# sensebox.net
KiCad netlist of a schematic drawn in EAGLE
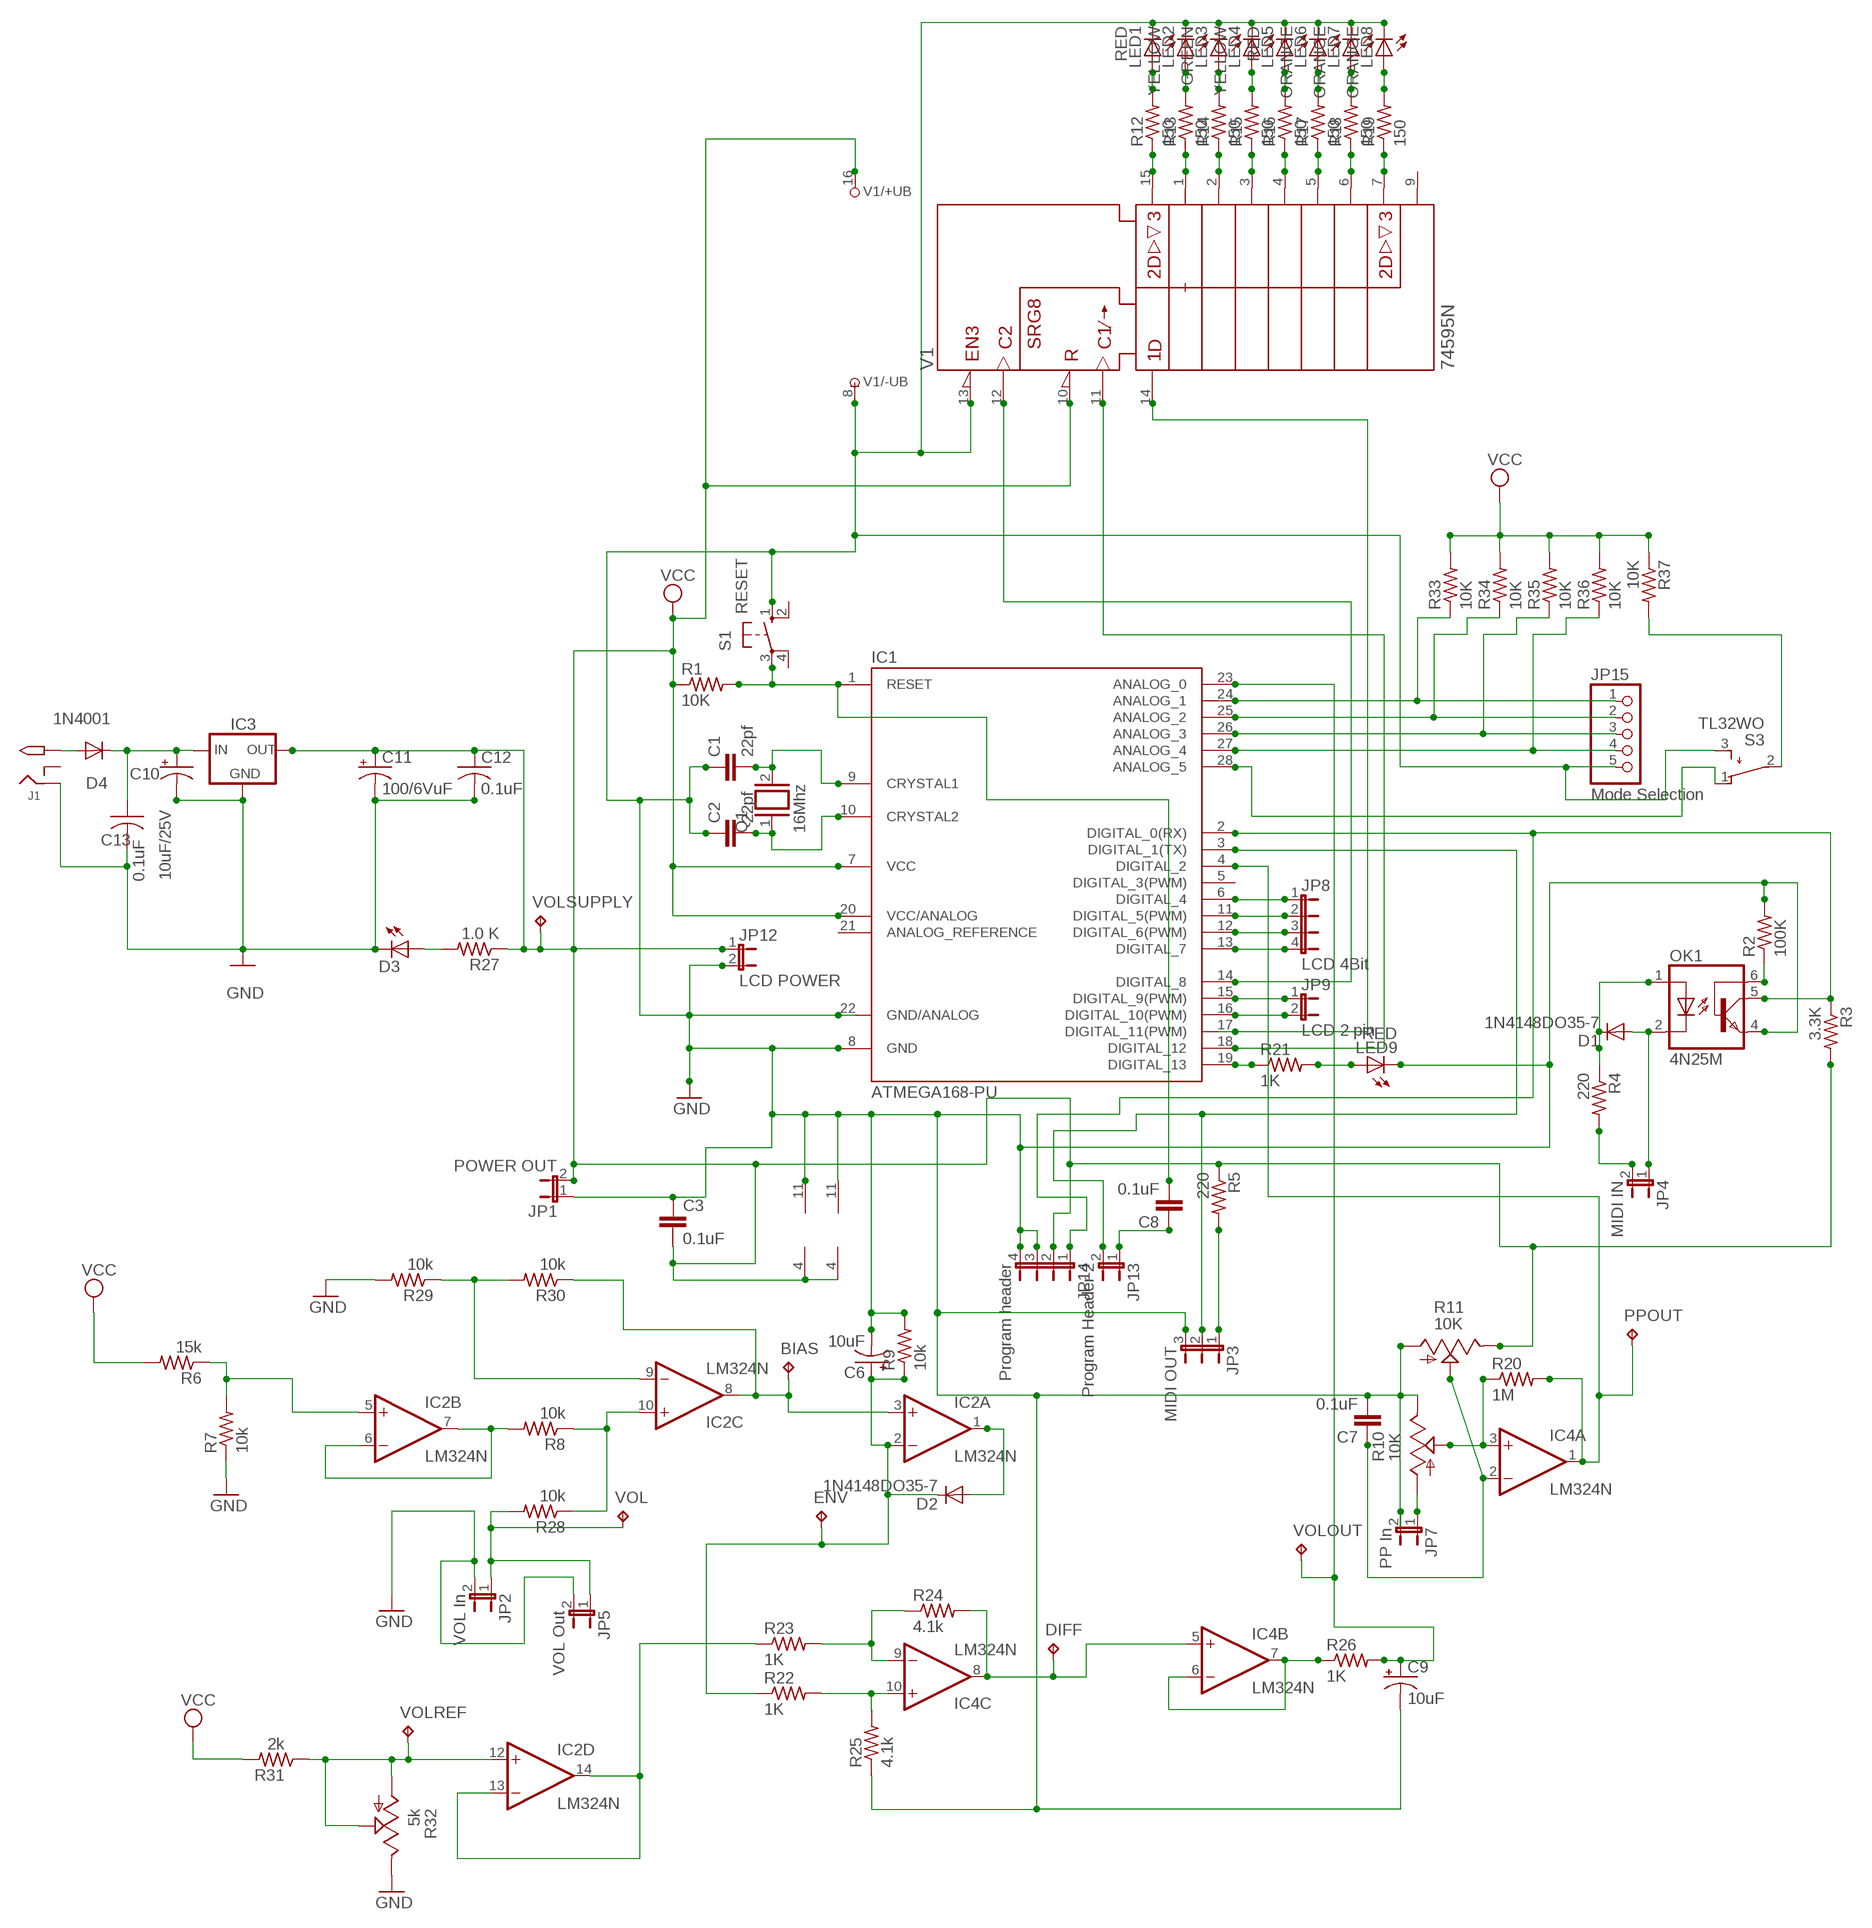
[diagram p0: schematic, sheet 1]

(export (version "E")
  (design (tool "Eeschema 10.0.6"))
  (components
    (comp (ref "BIAS")
      (value "TP1X1")
      (footprint "eagle-import:TP1X1")
      (libsource (lib "eagle-import") (part "TP1X1"))
    )
    (comp (ref "C1")
      (value "22pf")
      (footprint "eagle-import:C2.5-2")
      (libsource (lib "eagle-import") (part "C2.5/2"))
    )
    (comp (ref "C2")
      (value "22pf")
      (footprint "eagle-import:C2.5-2")
      (libsource (lib "eagle-import") (part "C2.5/2"))
    )
    (comp (ref "C3")
      (value "0.1uF")
      (footprint "eagle-import:C5B2.5")
      (libsource (lib "eagle-import") (part "C5/2.5"))
    )
    (comp (ref "C6")
      (value "10uF")
      (footprint "eagle-import:E5-8,5")
      (libsource (lib "eagle-import") (part "rcl_CPOL-USE5-8.5"))
    )
    (comp (ref "C7")
      (value "0.1uF")
      (footprint "eagle-import:C5B2.5")
      (libsource (lib "eagle-import") (part "C5/2.5"))
    )
    (comp (ref "C8")
      (value "0.1uF")
      (footprint "eagle-import:C2.5-2")
      (libsource (lib "eagle-import") (part "C2.5/2"))
    )
    (comp (ref "C9")
      (value "10uF")
      (footprint "eagle-import:E5-8,5")
      (libsource (lib "eagle-import") (part "rcl_CPOL-USE5-8.5"))
    )
    (comp (ref "C10")
      (value "10uF/25V")
      (footprint "eagle-import:E2,5-6")
      (libsource (lib "eagle-import") (part "CPOL-USE2.5-6"))
    )
    (comp (ref "C11")
      (value "100/6VuF")
      (footprint "eagle-import:E2,5-6")
      (libsource (lib "eagle-import") (part "CPOL-USE2.5-6"))
    )
    (comp (ref "C12")
      (value "0.1uF")
      (footprint "eagle-import:C025-025X050")
      (libsource (lib "eagle-import") (part "C-US025-025X050"))
    )
    (comp (ref "C13")
      (value "0.1uF")
      (footprint "eagle-import:C025-025X050")
      (libsource (lib "eagle-import") (part "C-US025-025X050"))
    )
    (comp (ref "D1")
      (value "1N4148DO35-7")
      (footprint "eagle-import:DO35-7")
      (libsource (lib "eagle-import") (part "1N4148DO35-7"))
    )
    (comp (ref "D2")
      (value "1N4148DO35-7")
      (footprint "eagle-import:DO35-7")
      (libsource (lib "eagle-import") (part "1N4148DO35-7"))
    )
    (comp (ref "D3")
      (value "GREEN")
      (footprint "eagle-import:LED3MM")
      (libsource (lib "eagle-import") (part "minimidi_LED3MM"))
    )
    (comp (ref "D4")
      (value "1N4001")
      (footprint "eagle-import:DO41-10")
      (libsource (lib "eagle-import") (part "1N4004"))
    )
    (comp (ref "DIFF")
      (value "TP1X1")
      (footprint "eagle-import:TP1X1")
      (libsource (lib "eagle-import") (part "TP1X1"))
    )
    (comp (ref "ENV")
      (value "TP1X1")
      (footprint "eagle-import:TP1X1")
      (libsource (lib "eagle-import") (part "TP1X1"))
    )
    (comp (ref "IC1")
      (value "ATMEGA168-PU")
      (footprint "eagle-import:DIL28-3")
      (libsource (lib "eagle-import") (part "ATMEGA168-PU"))
    )
    (comp (ref "IC2")
      (value "LM324N")
      (footprint "eagle-import:DIL14")
      (libsource (lib "eagle-import") (part "LM324N"))
    )
    (comp (ref "IC3")
      (value "+5v 7805")
      (footprint "eagle-import:78XXS")
      (libsource (lib "eagle-import") (part "78XXS"))
    )
    (comp (ref "IC4")
      (value "LM324N")
      (footprint "eagle-import:DIL14")
      (libsource (lib "eagle-import") (part "LM324N"))
    )
    (comp (ref "J1")
      (value "2.1MMJACK")
      (footprint "eagle-import:PJ-102A")
      (libsource (lib "eagle-import") (part "2.1MMJACK"))
    )
    (comp (ref "JP1")
      (value "POWER OUT")
      (footprint "eagle-import:JP1")
      (libsource (lib "eagle-import") (part "JP1E"))
    )
    (comp (ref "JP2")
      (value "VOL In")
      (footprint "eagle-import:JP1")
      (libsource (lib "eagle-import") (part "JP1E"))
    )
    (comp (ref "JP3")
      (value "MIDI OUT")
      (footprint "eagle-import:JP2")
      (libsource (lib "eagle-import") (part "JP2E"))
    )
    (comp (ref "JP4")
      (value "MIDI IN")
      (footprint "eagle-import:JP1")
      (libsource (lib "eagle-import") (part "JP1E"))
    )
    (comp (ref "JP5")
      (value "VOL Out")
      (footprint "eagle-import:JP1")
      (libsource (lib "eagle-import") (part "JP1E"))
    )
    (comp (ref "JP7")
      (value "PP In")
      (footprint "eagle-import:JP1")
      (libsource (lib "eagle-import") (part "JP1E"))
    )
    (comp (ref "JP8")
      (value "LCD 4Bit")
      (footprint "eagle-import:JP4")
      (libsource (lib "eagle-import") (part "JP4E"))
    )
    (comp (ref "JP9")
      (value "LCD 2 pin")
      (footprint "eagle-import:JP1")
      (libsource (lib "eagle-import") (part "JP1E"))
    )
    (comp (ref "JP12")
      (value "LCD POWER")
      (footprint "eagle-import:JP1")
      (libsource (lib "eagle-import") (part "JP1E"))
    )
    (comp (ref "JP13")
      (value "Program Header 2")
      (footprint "eagle-import:JP1")
      (libsource (lib "eagle-import") (part "JP1E"))
    )
    (comp (ref "JP14")
      (value "Program header")
      (footprint "eagle-import:JP4")
      (libsource (lib "eagle-import") (part "JP4E"))
    )
    (comp (ref "JP15")
      (value "Mode Selection")
      (footprint "eagle-import:1X05")
      (libsource (lib "eagle-import") (part "PINHD-1X5"))
    )
    (comp (ref "LED1")
      (value "RED")
      (footprint "eagle-import:LED5MM")
      (libsource (lib "eagle-import") (part "LED5MM"))
    )
    (comp (ref "LED2")
      (value "YELLOW")
      (footprint "eagle-import:LED5MM")
      (libsource (lib "eagle-import") (part "LED5MM"))
    )
    (comp (ref "LED3")
      (value "GREEN")
      (footprint "eagle-import:LED5MM")
      (libsource (lib "eagle-import") (part "LED5MM"))
    )
    (comp (ref "LED4")
      (value "YELLOW")
      (footprint "eagle-import:LED5MM")
      (libsource (lib "eagle-import") (part "LED5MM"))
    )
    (comp (ref "LED5")
      (value "RED")
      (footprint "eagle-import:LED5MM")
      (libsource (lib "eagle-import") (part "LED5MM"))
    )
    (comp (ref "LED6")
      (value "ORANGE")
      (footprint "eagle-import:LED5MM")
      (libsource (lib "eagle-import") (part "LED5MM"))
    )
    (comp (ref "LED7")
      (value "ORANGE")
      (footprint "eagle-import:LED5MM")
      (libsource (lib "eagle-import") (part "LED5MM"))
    )
    (comp (ref "LED8")
      (value "ORANGE")
      (footprint "eagle-import:LED5MM")
      (libsource (lib "eagle-import") (part "LED5MM"))
    )
    (comp (ref "LED9")
      (value "RED")
      (footprint "eagle-import:LED5MM")
      (libsource (lib "eagle-import") (part "LED5MM"))
    )
    (comp (ref "OK1")
      (value "4N25M")
      (footprint "eagle-import:DIL06")
      (libsource (lib "eagle-import") (part "4N?M25"))
    )
    (comp (ref "PPOUT")
      (value "TP1X1")
      (footprint "eagle-import:TP1X1")
      (libsource (lib "eagle-import") (part "TP1X1"))
    )
    (comp (ref "Q1")
      (value "16Mhz")
      (footprint "eagle-import:Q")
      (libsource (lib "eagle-import") (part "XTAL"))
    )
    (comp (ref "R1")
      (value "10K")
      (footprint "eagle-import:0207_7")
      (libsource (lib "eagle-import") (part "resistor_R-US_0207/7"))
    )
    (comp (ref "R2")
      (value "100K")
      (footprint "eagle-import:0207_7")
      (libsource (lib "eagle-import") (part "resistor_R-US_0207/7"))
    )
    (comp (ref "R3")
      (value "3.3K")
      (footprint "eagle-import:0207_7")
      (libsource (lib "eagle-import") (part "resistor_R-US_0207/7"))
    )
    (comp (ref "R4")
      (value "220")
      (footprint "eagle-import:0207_7")
      (libsource (lib "eagle-import") (part "resistor_R-US_0207/7"))
    )
    (comp (ref "R5")
      (value "220")
      (footprint "eagle-import:0207_7")
      (libsource (lib "eagle-import") (part "resistor_R-US_0207/7"))
    )
    (comp (ref "R6")
      (value "15k")
      (footprint "eagle-import:0207_10")
      (libsource (lib "eagle-import") (part "rcl_R-US_0207/10"))
    )
    (comp (ref "R7")
      (value "10k")
      (footprint "eagle-import:0207_10")
      (libsource (lib "eagle-import") (part "rcl_R-US_0207/10"))
    )
    (comp (ref "R8")
      (value "10k")
      (footprint "eagle-import:0207_10")
      (libsource (lib "eagle-import") (part "rcl_R-US_0207/10"))
    )
    (comp (ref "R9")
      (value "10k")
      (footprint "eagle-import:0207_7")
      (libsource (lib "eagle-import") (part "resistor_R-US_0207/7"))
    )
    (comp (ref "R10")
      (value "10K")
      (footprint "eagle-import:B64Y")
      (libsource (lib "eagle-import") (part "TRIM_US-B64Y"))
    )
    (comp (ref "R11")
      (value "10K")
      (footprint "eagle-import:B64Y")
      (libsource (lib "eagle-import") (part "TRIM_US-B64Y"))
    )
    (comp (ref "R12")
      (value "150")
      (footprint "eagle-import:0207_7")
      (libsource (lib "eagle-import") (part "resistor_R-US_0207/7"))
    )
    (comp (ref "R13")
      (value "150")
      (footprint "eagle-import:0207_7")
      (libsource (lib "eagle-import") (part "resistor_R-US_0207/7"))
    )
    (comp (ref "R14")
      (value "150")
      (footprint "eagle-import:0207_7")
      (libsource (lib "eagle-import") (part "resistor_R-US_0207/7"))
    )
    (comp (ref "R15")
      (value "150")
      (footprint "eagle-import:0207_7")
      (libsource (lib "eagle-import") (part "resistor_R-US_0207/7"))
    )
    (comp (ref "R16")
      (value "150")
      (footprint "eagle-import:0207_7")
      (libsource (lib "eagle-import") (part "resistor_R-US_0207/7"))
    )
    (comp (ref "R17")
      (value "150")
      (footprint "eagle-import:0207_7")
      (libsource (lib "eagle-import") (part "resistor_R-US_0207/7"))
    )
    (comp (ref "R18")
      (value "150")
      (footprint "eagle-import:0207_7")
      (libsource (lib "eagle-import") (part "resistor_R-US_0207/7"))
    )
    (comp (ref "R19")
      (value "150")
      (footprint "eagle-import:0207_7")
      (libsource (lib "eagle-import") (part "resistor_R-US_0207/7"))
    )
    (comp (ref "R20")
      (value "1M")
      (footprint "eagle-import:0207_7")
      (libsource (lib "eagle-import") (part "resistor_R-US_0207/7"))
    )
    (comp (ref "R21")
      (value "1K")
      (footprint "eagle-import:0207_7")
      (libsource (lib "eagle-import") (part "resistor_R-US_0207/7"))
    )
    (comp (ref "R22")
      (value "1K")
      (footprint "eagle-import:0207_7")
      (libsource (lib "eagle-import") (part "resistor_R-US_0207/7"))
    )
    (comp (ref "R23")
      (value "1K")
      (footprint "eagle-import:0207_7")
      (libsource (lib "eagle-import") (part "resistor_R-US_0207/7"))
    )
    (comp (ref "R24")
      (value "4.1k")
      (footprint "eagle-import:0207_7")
      (libsource (lib "eagle-import") (part "resistor_R-US_0207/7"))
    )
    (comp (ref "R25")
      (value "4.1k")
      (footprint "eagle-import:0207_7")
      (libsource (lib "eagle-import") (part "resistor_R-US_0207/7"))
    )
    (comp (ref "R26")
      (value "1K")
      (footprint "eagle-import:0207_7")
      (libsource (lib "eagle-import") (part "resistor_R-US_0207/7"))
    )
    (comp (ref "R27")
      (value "1.0 K")
      (footprint "eagle-import:0207_5V")
      (libsource (lib "eagle-import") (part "R-US_0207/5V"))
    )
    (comp (ref "R28")
      (value "10k")
      (footprint "eagle-import:0207_10")
      (libsource (lib "eagle-import") (part "resistor_R-US_0207/10"))
    )
    (comp (ref "R29")
      (value "10k")
      (footprint "eagle-import:0207_10")
      (libsource (lib "eagle-import") (part "rcl_R-US_0207/10"))
    )
    (comp (ref "R30")
      (value "10k")
      (footprint "eagle-import:0207_10")
      (libsource (lib "eagle-import") (part "resistor_R-US_0207/10"))
    )
    (comp (ref "R31")
      (value "2k")
      (footprint "eagle-import:0207_10")
      (libsource (lib "eagle-import") (part "rcl_R-US_0207/10"))
    )
    (comp (ref "R32")
      (value "5k")
      (footprint "eagle-import:B64Y")
      (libsource (lib "eagle-import") (part "TRIM_US-B64Y"))
    )
    (comp (ref "R33")
      (value "10K")
      (footprint "eagle-import:0207_7")
      (libsource (lib "eagle-import") (part "resistor_R-US_0207/7"))
    )
    (comp (ref "R34")
      (value "10K")
      (footprint "eagle-import:0207_7")
      (libsource (lib "eagle-import") (part "resistor_R-US_0207/7"))
    )
    (comp (ref "R35")
      (value "10K")
      (footprint "eagle-import:0207_7")
      (libsource (lib "eagle-import") (part "resistor_R-US_0207/7"))
    )
    (comp (ref "R36")
      (value "10K")
      (footprint "eagle-import:0207_7")
      (libsource (lib "eagle-import") (part "resistor_R-US_0207/7"))
    )
    (comp (ref "R37")
      (value "10K")
      (footprint "eagle-import:0207_7")
      (libsource (lib "eagle-import") (part "resistor_R-US_0207/7"))
    )
    (comp (ref "S1")
      (value "RESET")
      (footprint "eagle-import:B3F-10XX")
      (libsource (lib "eagle-import") (part "10-XX"))
    )
    (comp (ref "S3")
      (value "TL32WO")
      (footprint "eagle-import:TL3XWO")
      (libsource (lib "eagle-import") (part "TL32WO"))
    )
    (comp (ref "V1")
      (value "74595N")
      (footprint "eagle-import:DIL16")
      (libsource (lib "eagle-import") (part "74595N"))
    )
    (comp (ref "VOL")
      (value "TP1X1")
      (footprint "eagle-import:TP1X1")
      (libsource (lib "eagle-import") (part "TP1X1"))
    )
    (comp (ref "VOLOUT")
      (value "TP1X1")
      (footprint "eagle-import:TP1X1")
      (libsource (lib "eagle-import") (part "TP1X1"))
    )
    (comp (ref "VOLREF")
      (value "TP1X1")
      (footprint "eagle-import:TP1X1")
      (libsource (lib "eagle-import") (part "TP1X1"))
    )
    (comp (ref "VOLSUPPLY")
      (value "TP1X1")
      (footprint "eagle-import:TP1X1")
      (libsource (lib "eagle-import") (part "TP1X1"))
    )
  )
  (nets
    (net (code "1") (name "GND") (class "Default")
      (node (ref "C1") (pin "1") (pinfunction "1_1") (pintype "passive"))
      (node (ref "C10") (pin "-") (pinfunction "-_-") (pintype "passive"))
      (node (ref "C11") (pin "-") (pinfunction "-_-") (pintype "passive"))
      (node (ref "C12") (pin "2") (pinfunction "2_2") (pintype "passive"))
      (node (ref "C13") (pin "2") (pinfunction "2_2") (pintype "passive"))
      (node (ref "C2") (pin "1") (pinfunction "1_1") (pintype "passive"))
      (node (ref "C3") (pin "1") (pinfunction "1_1") (pintype "passive"))
      (node (ref "C6") (pin "-") (pinfunction "-_-") (pintype "passive"))
      (node (ref "C7") (pin "2") (pinfunction "2_2") (pintype "passive"))
      (node (ref "C9") (pin "-") (pinfunction "-_-") (pintype "passive"))
      (node (ref "D3") (pin "K") (pinfunction "C_K") (pintype "passive"))
      (node (ref "IC1") (pin "22") (pinfunction "GND/ANALOG_22") (pintype "power_in"))
      (node (ref "IC1") (pin "8") (pinfunction "GND_8") (pintype "power_in"))
      (node (ref "IC2") (pin "11") (pinfunction "V-_11") (pintype "power_in"))
      (node (ref "IC3") (pin "GND") (pinfunction "GND_GND") (pintype "input"))
      (node (ref "IC4") (pin "11") (pinfunction "V-_11") (pintype "power_in"))
      (node (ref "J1") (pin "RING") (pinfunction "RING_RING") (pintype "bidirectional"))
      (node (ref "JP1") (pin "1") (pinfunction "1_1") (pintype "passive"))
      (node (ref "JP12") (pin "2") (pinfunction "2_2") (pintype "passive"))
      (node (ref "JP14") (pin "3") (pinfunction "3_3") (pintype "passive"))
      (node (ref "JP14") (pin "4") (pinfunction "4_4") (pintype "passive"))
      (node (ref "JP15") (pin "5") (pinfunction "5_5") (pintype "passive"))
      (node (ref "JP2") (pin "2") (pinfunction "2_2") (pintype "passive"))
      (node (ref "JP3") (pin "3") (pinfunction "3_3") (pintype "passive"))
      (node (ref "JP5") (pin "2") (pinfunction "2_2") (pintype "passive"))
      (node (ref "JP7") (pin "2") (pinfunction "2_2") (pintype "passive"))
      (node (ref "LED1") (pin "K") (pinfunction "C_K") (pintype "passive"))
      (node (ref "LED2") (pin "K") (pinfunction "C_K") (pintype "passive"))
      (node (ref "LED3") (pin "K") (pinfunction "C_K") (pintype "passive"))
      (node (ref "LED4") (pin "K") (pinfunction "C_K") (pintype "passive"))
      (node (ref "LED5") (pin "K") (pinfunction "C_K") (pintype "passive"))
      (node (ref "LED6") (pin "K") (pinfunction "C_K") (pintype "passive"))
      (node (ref "LED7") (pin "K") (pinfunction "C_K") (pintype "passive"))
      (node (ref "LED8") (pin "K") (pinfunction "C_K") (pintype "passive"))
      (node (ref "LED9") (pin "K") (pinfunction "C_K") (pintype "passive"))
      (node (ref "OK1") (pin "4") (pinfunction "EMI_4") (pintype "passive"))
      (node (ref "R10") (pin "E") (pinfunction "E_E") (pintype "passive"))
      (node (ref "R11") (pin "A") (pinfunction "A_A") (pintype "passive"))
      (node (ref "R2") (pin "2") (pinfunction "2_2") (pintype "passive"))
      (node (ref "R25") (pin "1") (pinfunction "1_1") (pintype "passive"))
      (node (ref "R29") (pin "2") (pinfunction "2_2") (pintype "passive"))
      (node (ref "R32") (pin "E") (pinfunction "E_E") (pintype "passive"))
      (node (ref "R7") (pin "1") (pinfunction "1_1") (pintype "passive"))
      (node (ref "R9") (pin "2") (pinfunction "2_2") (pintype "passive"))
      (node (ref "S1") (pin "1") (pinfunction "S_1") (pintype "passive"))
      (node (ref "S3") (pin "3") (pinfunction "S_3") (pintype "passive"))
      (node (ref "V1") (pin "13") (pinfunction "~{G}_13") (pintype "input"))
      (node (ref "V1") (pin "8") (pinfunction "-UB_8") (pintype "power_in"))
    )
    (net (code "2") (name "Net-(BIAS-TP)") (class "Default")
      (node (ref "BIAS") (pin "P$1") (pinfunction "TP_P$1") (pintype "input"))
      (node (ref "IC2") (pin "3") (pinfunction "+IN_3") (pintype "input"))
      (node (ref "IC2") (pin "8") (pinfunction "OUT_8") (pintype "output"))
      (node (ref "R30") (pin "1") (pinfunction "1_1") (pintype "passive"))
    )
    (net (code "3") (name "Net-(C8-Pad1)") (class "Default")
      (node (ref "C8") (pin "1") (pinfunction "1_1") (pintype "passive"))
      (node (ref "JP13") (pin "1") (pinfunction "1_1") (pintype "passive"))
    )
    (net (code "4") (name "Net-(C10-Pad+)") (class "Default")
      (node (ref "C10") (pin "+") (pinfunction "+_+") (pintype "passive"))
      (node (ref "C13") (pin "1") (pinfunction "1_1") (pintype "passive"))
      (node (ref "D4") (pin "C") (pinfunction "C_C") (pintype "passive"))
      (node (ref "IC3") (pin "IN") (pinfunction "IN_IN") (pintype "input"))
    )
    (net (code "5") (name "Net-(D3-PadA)") (class "Default")
      (node (ref "D3") (pin "A") (pinfunction "A_A") (pintype "passive"))
      (node (ref "R27") (pin "2") (pinfunction "2_2") (pintype "passive"))
    )
    (net (code "6") (name "Net-(D4-PadA)") (class "Default")
      (node (ref "D4") (pin "A") (pinfunction "A_A") (pintype "passive"))
      (node (ref "J1") (pin "TIP") (pinfunction "TIP_TIP") (pintype "bidirectional"))
    )
    (net (code "7") (name "Net-(DIFF-TP)") (class "Default")
      (node (ref "DIFF") (pin "P$1") (pinfunction "TP_P$1") (pintype "input"))
      (node (ref "IC4") (pin "5") (pinfunction "+IN_5") (pintype "input"))
      (node (ref "IC4") (pin "8") (pinfunction "OUT_8") (pintype "output"))
      (node (ref "R24") (pin "2") (pinfunction "2_2") (pintype "passive"))
    )
    (net (code "8") (name "Net-(ENV-TP)") (class "Default")
      (node (ref "C6") (pin "+") (pinfunction "+_+") (pintype "passive"))
      (node (ref "D2") (pin "C") (pinfunction "C_C") (pintype "passive"))
      (node (ref "ENV") (pin "P$1") (pinfunction "TP_P$1") (pintype "input"))
      (node (ref "IC2") (pin "2") (pinfunction "-IN_2") (pintype "input"))
      (node (ref "R22") (pin "1") (pinfunction "1_1") (pintype "passive"))
      (node (ref "R9") (pin "1") (pinfunction "1_1") (pintype "passive"))
    )
    (net (code "9") (name "Net-(IC1-ANALOG_0)") (class "Default")
      (node (ref "C9") (pin "+") (pinfunction "+_+") (pintype "passive"))
      (node (ref "IC1") (pin "23") (pinfunction "ANALOG_0_23") (pintype "bidirectional"))
      (node (ref "R26") (pin "2") (pinfunction "2_2") (pintype "passive"))
      (node (ref "VOLOUT") (pin "P$1") (pinfunction "TP_P$1") (pintype "input"))
    )
    (net (code "10") (name "Net-(IC1-ANALOG_1)") (class "Default")
      (node (ref "IC1") (pin "24") (pinfunction "ANALOG_1_24") (pintype "bidirectional"))
      (node (ref "JP15") (pin "1") (pinfunction "1_1") (pintype "passive"))
      (node (ref "R33") (pin "1") (pinfunction "1_1") (pintype "passive"))
    )
    (net (code "11") (name "Net-(IC1-ANALOG_2)") (class "Default")
      (node (ref "IC1") (pin "25") (pinfunction "ANALOG_2_25") (pintype "bidirectional"))
      (node (ref "JP15") (pin "2") (pinfunction "2_2") (pintype "passive"))
      (node (ref "R34") (pin "1") (pinfunction "1_1") (pintype "passive"))
    )
    (net (code "12") (name "Net-(IC1-ANALOG_3)") (class "Default")
      (node (ref "IC1") (pin "26") (pinfunction "ANALOG_3_26") (pintype "bidirectional"))
      (node (ref "JP15") (pin "3") (pinfunction "3_3") (pintype "passive"))
      (node (ref "R35") (pin "1") (pinfunction "1_1") (pintype "passive"))
    )
    (net (code "13") (name "Net-(IC1-ANALOG_4)") (class "Default")
      (node (ref "IC1") (pin "27") (pinfunction "ANALOG_4_27") (pintype "bidirectional"))
      (node (ref "JP15") (pin "4") (pinfunction "4_4") (pintype "passive"))
      (node (ref "R36") (pin "1") (pinfunction "1_1") (pintype "passive"))
    )
    (net (code "14") (name "Net-(IC1-ANALOG_5)") (class "Default")
      (node (ref "IC1") (pin "28") (pinfunction "ANALOG_5_28") (pintype "bidirectional"))
      (node (ref "S3") (pin "1") (pinfunction "O_1") (pintype "passive"))
    )
    (net (code "15") (name "Net-(IC1-CRYSTAL1)") (class "Default")
      (node (ref "C1") (pin "2") (pinfunction "2_2") (pintype "passive"))
      (node (ref "IC1") (pin "9") (pinfunction "CRYSTAL1_9") (pintype "bidirectional"))
      (node (ref "Q1") (pin "2") (pinfunction "2_2") (pintype "passive"))
    )
    (net (code "16") (name "Net-(IC1-CRYSTAL2)") (class "Default")
      (node (ref "C2") (pin "2") (pinfunction "2_2") (pintype "passive"))
      (node (ref "IC1") (pin "10") (pinfunction "CRYSTAL2_10") (pintype "bidirectional"))
      (node (ref "Q1") (pin "1") (pinfunction "1_1") (pintype "passive"))
    )
    (net (code "17") (name "Net-(IC1-DIGITAL_0(RX))") (class "Default")
      (node (ref "IC1") (pin "2") (pinfunction "DIGITAL_0(RX)_2") (pintype "bidirectional"))
      (node (ref "JP14") (pin "1") (pinfunction "1_1") (pintype "passive"))
      (node (ref "OK1") (pin "5") (pinfunction "COL_5") (pintype "passive"))
      (node (ref "R3") (pin "1") (pinfunction "1_1") (pintype "passive"))
    )
    (net (code "18") (name "Net-(IC1-DIGITAL_1(TX))") (class "Default")
      (node (ref "IC1") (pin "3") (pinfunction "DIGITAL_1(TX)_3") (pintype "bidirectional"))
      (node (ref "JP13") (pin "2") (pinfunction "2_2") (pintype "passive"))
      (node (ref "JP3") (pin "2") (pinfunction "2_2") (pintype "passive"))
    )
    (net (code "19") (name "Net-(IC1-DIGITAL_2)") (class "Default")
      (node (ref "IC1") (pin "4") (pinfunction "DIGITAL_2_4") (pintype "bidirectional"))
      (node (ref "IC4") (pin "1") (pinfunction "OUT_1") (pintype "output"))
      (node (ref "PPOUT") (pin "P$1") (pinfunction "TP_P$1") (pintype "input"))
      (node (ref "R20") (pin "2") (pinfunction "2_2") (pintype "passive"))
    )
    (net (code "20") (name "Net-(IC1-DIGITAL_4)") (class "Default")
      (node (ref "IC1") (pin "6") (pinfunction "DIGITAL_4_6") (pintype "bidirectional"))
      (node (ref "JP8") (pin "1") (pinfunction "1_1") (pintype "passive"))
    )
    (net (code "21") (name "Net-(IC1-DIGITAL_5(PWM))") (class "Default")
      (node (ref "IC1") (pin "11") (pinfunction "DIGITAL_5(PWM)_11") (pintype "bidirectional"))
      (node (ref "JP8") (pin "2") (pinfunction "2_2") (pintype "passive"))
    )
    (net (code "22") (name "Net-(IC1-DIGITAL_6(PWM))") (class "Default")
      (node (ref "IC1") (pin "12") (pinfunction "DIGITAL_6(PWM)_12") (pintype "bidirectional"))
      (node (ref "JP8") (pin "3") (pinfunction "3_3") (pintype "passive"))
    )
    (net (code "23") (name "Net-(IC1-DIGITAL_7)") (class "Default")
      (node (ref "IC1") (pin "13") (pinfunction "DIGITAL_7_13") (pintype "bidirectional"))
      (node (ref "JP8") (pin "4") (pinfunction "4_4") (pintype "passive"))
    )
    (net (code "24") (name "Net-(IC1-DIGITAL_8)") (class "Default")
      (node (ref "IC1") (pin "14") (pinfunction "DIGITAL_8_14") (pintype "bidirectional"))
      (node (ref "V1") (pin "12") (pinfunction "RCK_12") (pintype "input"))
    )
    (net (code "25") (name "Net-(IC1-DIGITAL_9(PWM))") (class "Default")
      (node (ref "IC1") (pin "15") (pinfunction "DIGITAL_9(PWM)_15") (pintype "bidirectional"))
      (node (ref "JP9") (pin "1") (pinfunction "1_1") (pintype "passive"))
    )
    (net (code "26") (name "Net-(IC1-DIGITAL_10(PWM))") (class "Default")
      (node (ref "IC1") (pin "16") (pinfunction "DIGITAL_10(PWM)_16") (pintype "bidirectional"))
      (node (ref "JP9") (pin "2") (pinfunction "2_2") (pintype "passive"))
    )
    (net (code "27") (name "Net-(IC1-DIGITAL_11(PWM))") (class "Default")
      (node (ref "IC1") (pin "17") (pinfunction "DIGITAL_11(PWM)_17") (pintype "bidirectional"))
      (node (ref "V1") (pin "14") (pinfunction "SER_14") (pintype "input"))
    )
    (net (code "28") (name "Net-(IC1-DIGITAL_12)") (class "Default")
      (node (ref "IC1") (pin "18") (pinfunction "DIGITAL_12_18") (pintype "bidirectional"))
      (node (ref "V1") (pin "11") (pinfunction "SRCK_11") (pintype "input"))
    )
    (net (code "29") (name "Net-(IC1-DIGITAL_13)") (class "Default")
      (node (ref "IC1") (pin "19") (pinfunction "DIGITAL_13_19") (pintype "bidirectional"))
      (node (ref "R21") (pin "1") (pinfunction "1_1") (pintype "passive"))
    )
    (net (code "30") (name "Net-(IC1-RESET)") (class "Default")
      (node (ref "C8") (pin "2") (pinfunction "2_2") (pintype "passive"))
      (node (ref "IC1") (pin "1") (pinfunction "RESET_1") (pintype "bidirectional"))
      (node (ref "R1") (pin "2") (pinfunction "2_2") (pintype "passive"))
      (node (ref "S1") (pin "3") (pinfunction "P_3") (pintype "passive"))
    )
    (net (code "31") (name "Net-(IC2A-OUT)") (class "Default")
      (node (ref "D2") (pin "A") (pinfunction "A_A") (pintype "passive"))
      (node (ref "IC2") (pin "1") (pinfunction "OUT_1") (pintype "output"))
    )
    (net (code "32") (name "Net-(IC2B-+IN)") (class "Default")
      (node (ref "IC2") (pin "5") (pinfunction "+IN_5") (pintype "input"))
      (node (ref "R6") (pin "1") (pinfunction "1_1") (pintype "passive"))
      (node (ref "R7") (pin "2") (pinfunction "2_2") (pintype "passive"))
    )
    (net (code "33") (name "Net-(IC2B--IN)") (class "Default")
      (node (ref "IC2") (pin "6") (pinfunction "-IN_6") (pintype "input"))
      (node (ref "IC2") (pin "7") (pinfunction "OUT_7") (pintype "output"))
      (node (ref "R8") (pin "2") (pinfunction "2_2") (pintype "passive"))
    )
    (net (code "34") (name "Net-(IC2C-+IN)") (class "Default")
      (node (ref "IC2") (pin "10") (pinfunction "+IN_10") (pintype "input"))
      (node (ref "R28") (pin "1") (pinfunction "1_1") (pintype "passive"))
      (node (ref "R8") (pin "1") (pinfunction "1_1") (pintype "passive"))
    )
    (net (code "35") (name "Net-(IC2C--IN)") (class "Default")
      (node (ref "IC2") (pin "9") (pinfunction "-IN_9") (pintype "input"))
      (node (ref "R29") (pin "1") (pinfunction "1_1") (pintype "passive"))
      (node (ref "R30") (pin "2") (pinfunction "2_2") (pintype "passive"))
    )
    (net (code "36") (name "Net-(IC2D-+IN)") (class "Default")
      (node (ref "IC2") (pin "12") (pinfunction "+IN_12") (pintype "input"))
      (node (ref "R31") (pin "1") (pinfunction "1_1") (pintype "passive"))
      (node (ref "R32") (pin "A") (pinfunction "A_A") (pintype "passive"))
      (node (ref "R32") (pin "S") (pinfunction "S_S") (pintype "passive"))
      (node (ref "VOLREF") (pin "P$1") (pinfunction "TP_P$1") (pintype "input"))
    )
    (net (code "37") (name "Net-(IC2D--IN)") (class "Default")
      (node (ref "IC2") (pin "13") (pinfunction "-IN_13") (pintype "input"))
      (node (ref "IC2") (pin "14") (pinfunction "OUT_14") (pintype "output"))
      (node (ref "R23") (pin "1") (pinfunction "1_1") (pintype "passive"))
    )
    (net (code "38") (name "Net-(IC4A-+IN)") (class "Default")
      (node (ref "IC4") (pin "3") (pinfunction "+IN_3") (pintype "input"))
      (node (ref "R10") (pin "S") (pinfunction "S_S") (pintype "passive"))
      (node (ref "R20") (pin "1") (pinfunction "1_1") (pintype "passive"))
    )
    (net (code "39") (name "Net-(IC4A--IN)") (class "Default")
      (node (ref "C7") (pin "1") (pinfunction "1_1") (pintype "passive"))
      (node (ref "IC4") (pin "2") (pinfunction "-IN_2") (pintype "input"))
      (node (ref "R11") (pin "S") (pinfunction "S_S") (pintype "passive"))
    )
    (net (code "40") (name "Net-(IC4B--IN)") (class "Default")
      (node (ref "IC4") (pin "6") (pinfunction "-IN_6") (pintype "input"))
      (node (ref "IC4") (pin "7") (pinfunction "OUT_7") (pintype "output"))
      (node (ref "R26") (pin "1") (pinfunction "1_1") (pintype "passive"))
    )
    (net (code "41") (name "Net-(IC4C-+IN)") (class "Default")
      (node (ref "IC4") (pin "10") (pinfunction "+IN_10") (pintype "input"))
      (node (ref "R22") (pin "2") (pinfunction "2_2") (pintype "passive"))
      (node (ref "R25") (pin "2") (pinfunction "2_2") (pintype "passive"))
    )
    (net (code "42") (name "Net-(IC4C--IN)") (class "Default")
      (node (ref "IC4") (pin "9") (pinfunction "-IN_9") (pintype "input"))
      (node (ref "R23") (pin "2") (pinfunction "2_2") (pintype "passive"))
      (node (ref "R24") (pin "1") (pinfunction "1_1") (pintype "passive"))
    )
    (net (code "43") (name "Net-(JP3-Pad1)") (class "Default")
      (node (ref "JP3") (pin "1") (pinfunction "1_1") (pintype "passive"))
      (node (ref "R5") (pin "2") (pinfunction "2_2") (pintype "passive"))
    )
    (net (code "44") (name "Net-(JP4-Pad2)") (class "Default")
      (node (ref "JP4") (pin "2") (pinfunction "2_2") (pintype "passive"))
      (node (ref "R4") (pin "2") (pinfunction "2_2") (pintype "passive"))
    )
    (net (code "45") (name "Net-(JP7-Pad1)") (class "Default")
      (node (ref "JP7") (pin "1") (pinfunction "1_1") (pintype "passive"))
      (node (ref "R10") (pin "A") (pinfunction "A_A") (pintype "passive"))
    )
    (net (code "46") (name "Net-(LED1-PadA)") (class "Default")
      (node (ref "LED1") (pin "A") (pinfunction "A_A") (pintype "passive"))
      (node (ref "R12") (pin "2") (pinfunction "2_2") (pintype "passive"))
    )
    (net (code "47") (name "Net-(LED2-PadA)") (class "Default")
      (node (ref "LED2") (pin "A") (pinfunction "A_A") (pintype "passive"))
      (node (ref "R13") (pin "2") (pinfunction "2_2") (pintype "passive"))
    )
    (net (code "48") (name "Net-(LED3-PadA)") (class "Default")
      (node (ref "LED3") (pin "A") (pinfunction "A_A") (pintype "passive"))
      (node (ref "R14") (pin "2") (pinfunction "2_2") (pintype "passive"))
    )
    (net (code "49") (name "Net-(LED4-PadA)") (class "Default")
      (node (ref "LED4") (pin "A") (pinfunction "A_A") (pintype "passive"))
      (node (ref "R15") (pin "2") (pinfunction "2_2") (pintype "passive"))
    )
    (net (code "50") (name "Net-(LED5-PadA)") (class "Default")
      (node (ref "LED5") (pin "A") (pinfunction "A_A") (pintype "passive"))
      (node (ref "R16") (pin "2") (pinfunction "2_2") (pintype "passive"))
    )
    (net (code "51") (name "Net-(LED6-PadA)") (class "Default")
      (node (ref "LED6") (pin "A") (pinfunction "A_A") (pintype "passive"))
      (node (ref "R17") (pin "2") (pinfunction "2_2") (pintype "passive"))
    )
    (net (code "52") (name "Net-(LED7-PadA)") (class "Default")
      (node (ref "LED7") (pin "A") (pinfunction "A_A") (pintype "passive"))
      (node (ref "R18") (pin "2") (pinfunction "2_2") (pintype "passive"))
    )
    (net (code "53") (name "Net-(LED8-PadA)") (class "Default")
      (node (ref "LED8") (pin "A") (pinfunction "A_A") (pintype "passive"))
      (node (ref "R19") (pin "2") (pinfunction "2_2") (pintype "passive"))
    )
    (net (code "54") (name "Net-(LED9-PadA)") (class "Default")
      (node (ref "LED9") (pin "A") (pinfunction "A_A") (pintype "passive"))
      (node (ref "R21") (pin "2") (pinfunction "2_2") (pintype "passive"))
    )
    (net (code "55") (name "Net-(OK1-A)") (class "Default")
      (node (ref "D1") (pin "C") (pinfunction "C_C") (pintype "passive"))
      (node (ref "OK1") (pin "1") (pinfunction "A_1") (pintype "passive"))
      (node (ref "R4") (pin "1") (pinfunction "1_1") (pintype "passive"))
    )
    (net (code "56") (name "Net-(OK1-BAS)") (class "Default")
      (node (ref "OK1") (pin "6") (pinfunction "BAS_6") (pintype "passive"))
      (node (ref "R2") (pin "1") (pinfunction "1_1") (pintype "passive"))
    )
    (net (code "57") (name "Net-(OK1-C)") (class "Default")
      (node (ref "D1") (pin "A") (pinfunction "A_A") (pintype "passive"))
      (node (ref "JP4") (pin "1") (pinfunction "1_1") (pintype "passive"))
      (node (ref "OK1") (pin "2") (pinfunction "C_2") (pintype "passive"))
    )
    (net (code "58") (name "Net-(S3-P)") (class "Default")
      (node (ref "R37") (pin "2") (pinfunction "2_2") (pintype "passive"))
      (node (ref "S3") (pin "2") (pinfunction "P_2") (pintype "passive"))
    )
    (net (code "59") (name "Net-(V1C-QA)") (class "Default")
      (node (ref "R12") (pin "1") (pinfunction "1_1") (pintype "passive"))
      (node (ref "V1") (pin "15") (pinfunction "QA_15") (pintype "tri_state"))
    )
    (net (code "60") (name "Net-(V1C-QB)") (class "Default")
      (node (ref "R13") (pin "1") (pinfunction "1_1") (pintype "passive"))
      (node (ref "V1") (pin "1") (pinfunction "QB_1") (pintype "tri_state"))
    )
    (net (code "61") (name "Net-(V1C-QC)") (class "Default")
      (node (ref "R14") (pin "1") (pinfunction "1_1") (pintype "passive"))
      (node (ref "V1") (pin "2") (pinfunction "QC_2") (pintype "tri_state"))
    )
    (net (code "62") (name "Net-(V1C-QD)") (class "Default")
      (node (ref "R15") (pin "1") (pinfunction "1_1") (pintype "passive"))
      (node (ref "V1") (pin "3") (pinfunction "QD_3") (pintype "tri_state"))
    )
    (net (code "63") (name "Net-(V1C-QE)") (class "Default")
      (node (ref "R16") (pin "1") (pinfunction "1_1") (pintype "passive"))
      (node (ref "V1") (pin "4") (pinfunction "QE_4") (pintype "tri_state"))
    )
    (net (code "64") (name "Net-(V1C-QF)") (class "Default")
      (node (ref "R17") (pin "1") (pinfunction "1_1") (pintype "passive"))
      (node (ref "V1") (pin "5") (pinfunction "QF_5") (pintype "tri_state"))
    )
    (net (code "65") (name "Net-(V1C-QG)") (class "Default")
      (node (ref "R18") (pin "1") (pinfunction "1_1") (pintype "passive"))
      (node (ref "V1") (pin "6") (pinfunction "QG_6") (pintype "tri_state"))
    )
    (net (code "66") (name "Net-(V1C-QH)") (class "Default")
      (node (ref "R19") (pin "1") (pinfunction "1_1") (pintype "passive"))
      (node (ref "V1") (pin "7") (pinfunction "QH_7") (pintype "tri_state"))
    )
    (net (code "67") (name "Net-(VOL-TP)") (class "Default")
      (node (ref "JP2") (pin "1") (pinfunction "1_1") (pintype "passive"))
      (node (ref "JP5") (pin "1") (pinfunction "1_1") (pintype "passive"))
      (node (ref "R28") (pin "2") (pinfunction "2_2") (pintype "passive"))
      (node (ref "VOL") (pin "P$1") (pinfunction "TP_P$1") (pintype "input"))
    )
    (net (code "68") (name "VCC") (class "Default")
      (node (ref "C11") (pin "+") (pinfunction "+_+") (pintype "passive"))
      (node (ref "C12") (pin "1") (pinfunction "1_1") (pintype "passive"))
      (node (ref "C3") (pin "2") (pinfunction "2_2") (pintype "passive"))
      (node (ref "IC1") (pin "20") (pinfunction "VCC/ANALOG_20") (pintype "passive"))
      (node (ref "IC1") (pin "7") (pinfunction "VCC_7") (pintype "power_in"))
      (node (ref "IC2") (pin "4") (pinfunction "V+_4") (pintype "power_in"))
      (node (ref "IC3") (pin "OUT") (pinfunction "OUT_OUT") (pintype "passive"))
      (node (ref "IC4") (pin "4") (pinfunction "V+_4") (pintype "power_in"))
      (node (ref "JP1") (pin "2") (pinfunction "2_2") (pintype "passive"))
      (node (ref "JP12") (pin "1") (pinfunction "1_1") (pintype "passive"))
      (node (ref "JP14") (pin "2") (pinfunction "2_2") (pintype "passive"))
      (node (ref "R1") (pin "1") (pinfunction "1_1") (pintype "passive"))
      (node (ref "R11") (pin "E") (pinfunction "E_E") (pintype "passive"))
      (node (ref "R27") (pin "1") (pinfunction "1_1") (pintype "passive"))
      (node (ref "R3") (pin "2") (pinfunction "2_2") (pintype "passive"))
      (node (ref "R31") (pin "2") (pinfunction "2_2") (pintype "passive"))
      (node (ref "R33") (pin "2") (pinfunction "2_2") (pintype "passive"))
      (node (ref "R34") (pin "2") (pinfunction "2_2") (pintype "passive"))
      (node (ref "R35") (pin "2") (pinfunction "2_2") (pintype "passive"))
      (node (ref "R36") (pin "2") (pinfunction "2_2") (pintype "passive"))
      (node (ref "R37") (pin "1") (pinfunction "1_1") (pintype "passive"))
      (node (ref "R5") (pin "1") (pinfunction "1_1") (pintype "passive"))
      (node (ref "R6") (pin "2") (pinfunction "2_2") (pintype "passive"))
      (node (ref "V1") (pin "10") (pinfunction "~{SRCLR}_10") (pintype "input"))
      (node (ref "V1") (pin "16") (pinfunction "+UB_16") (pintype "power_in"))
      (node (ref "VOLSUPPLY") (pin "P$1") (pinfunction "TP_P$1") (pintype "input"))
    )
    (net (code "69") (name "unconnected-(IC1-ANALOG_REFERENCE-Pad21)") (class "Default")
      (node (ref "IC1") (pin "21") (pinfunction "ANALOG_REFERENCE_21") (pintype "passive"))
    )
    (net (code "70") (name "unconnected-(IC1-DIGITAL_3(PWM)-Pad5)") (class "Default")
      (node (ref "IC1") (pin "5") (pinfunction "DIGITAL_3(PWM)_5") (pintype "bidirectional"))
    )
    (net (code "71") (name "unconnected-(J1-PadRING_SW)") (class "Default")
      (node (ref "J1") (pin "RING_SW") (pinfunction "RING_SW_RING_SW") (pintype "bidirectional"))
    )
    (net (code "72") (name "unconnected-(S1-P1-Pad4)") (class "Default")
      (node (ref "S1") (pin "4") (pinfunction "P1_4") (pintype "passive"))
    )
    (net (code "73") (name "unconnected-(S1-S1-Pad2)") (class "Default")
      (node (ref "S1") (pin "2") (pinfunction "S1_2") (pintype "passive"))
    )
    (net (code "74") (name "unconnected-(V1C-QH*-Pad9)") (class "Default")
      (node (ref "V1") (pin "9") (pinfunction "QH*_9") (pintype "output"))
    )
  )
)
